# workshop.net
KiCad netlist of a schematic drawn in EAGLE
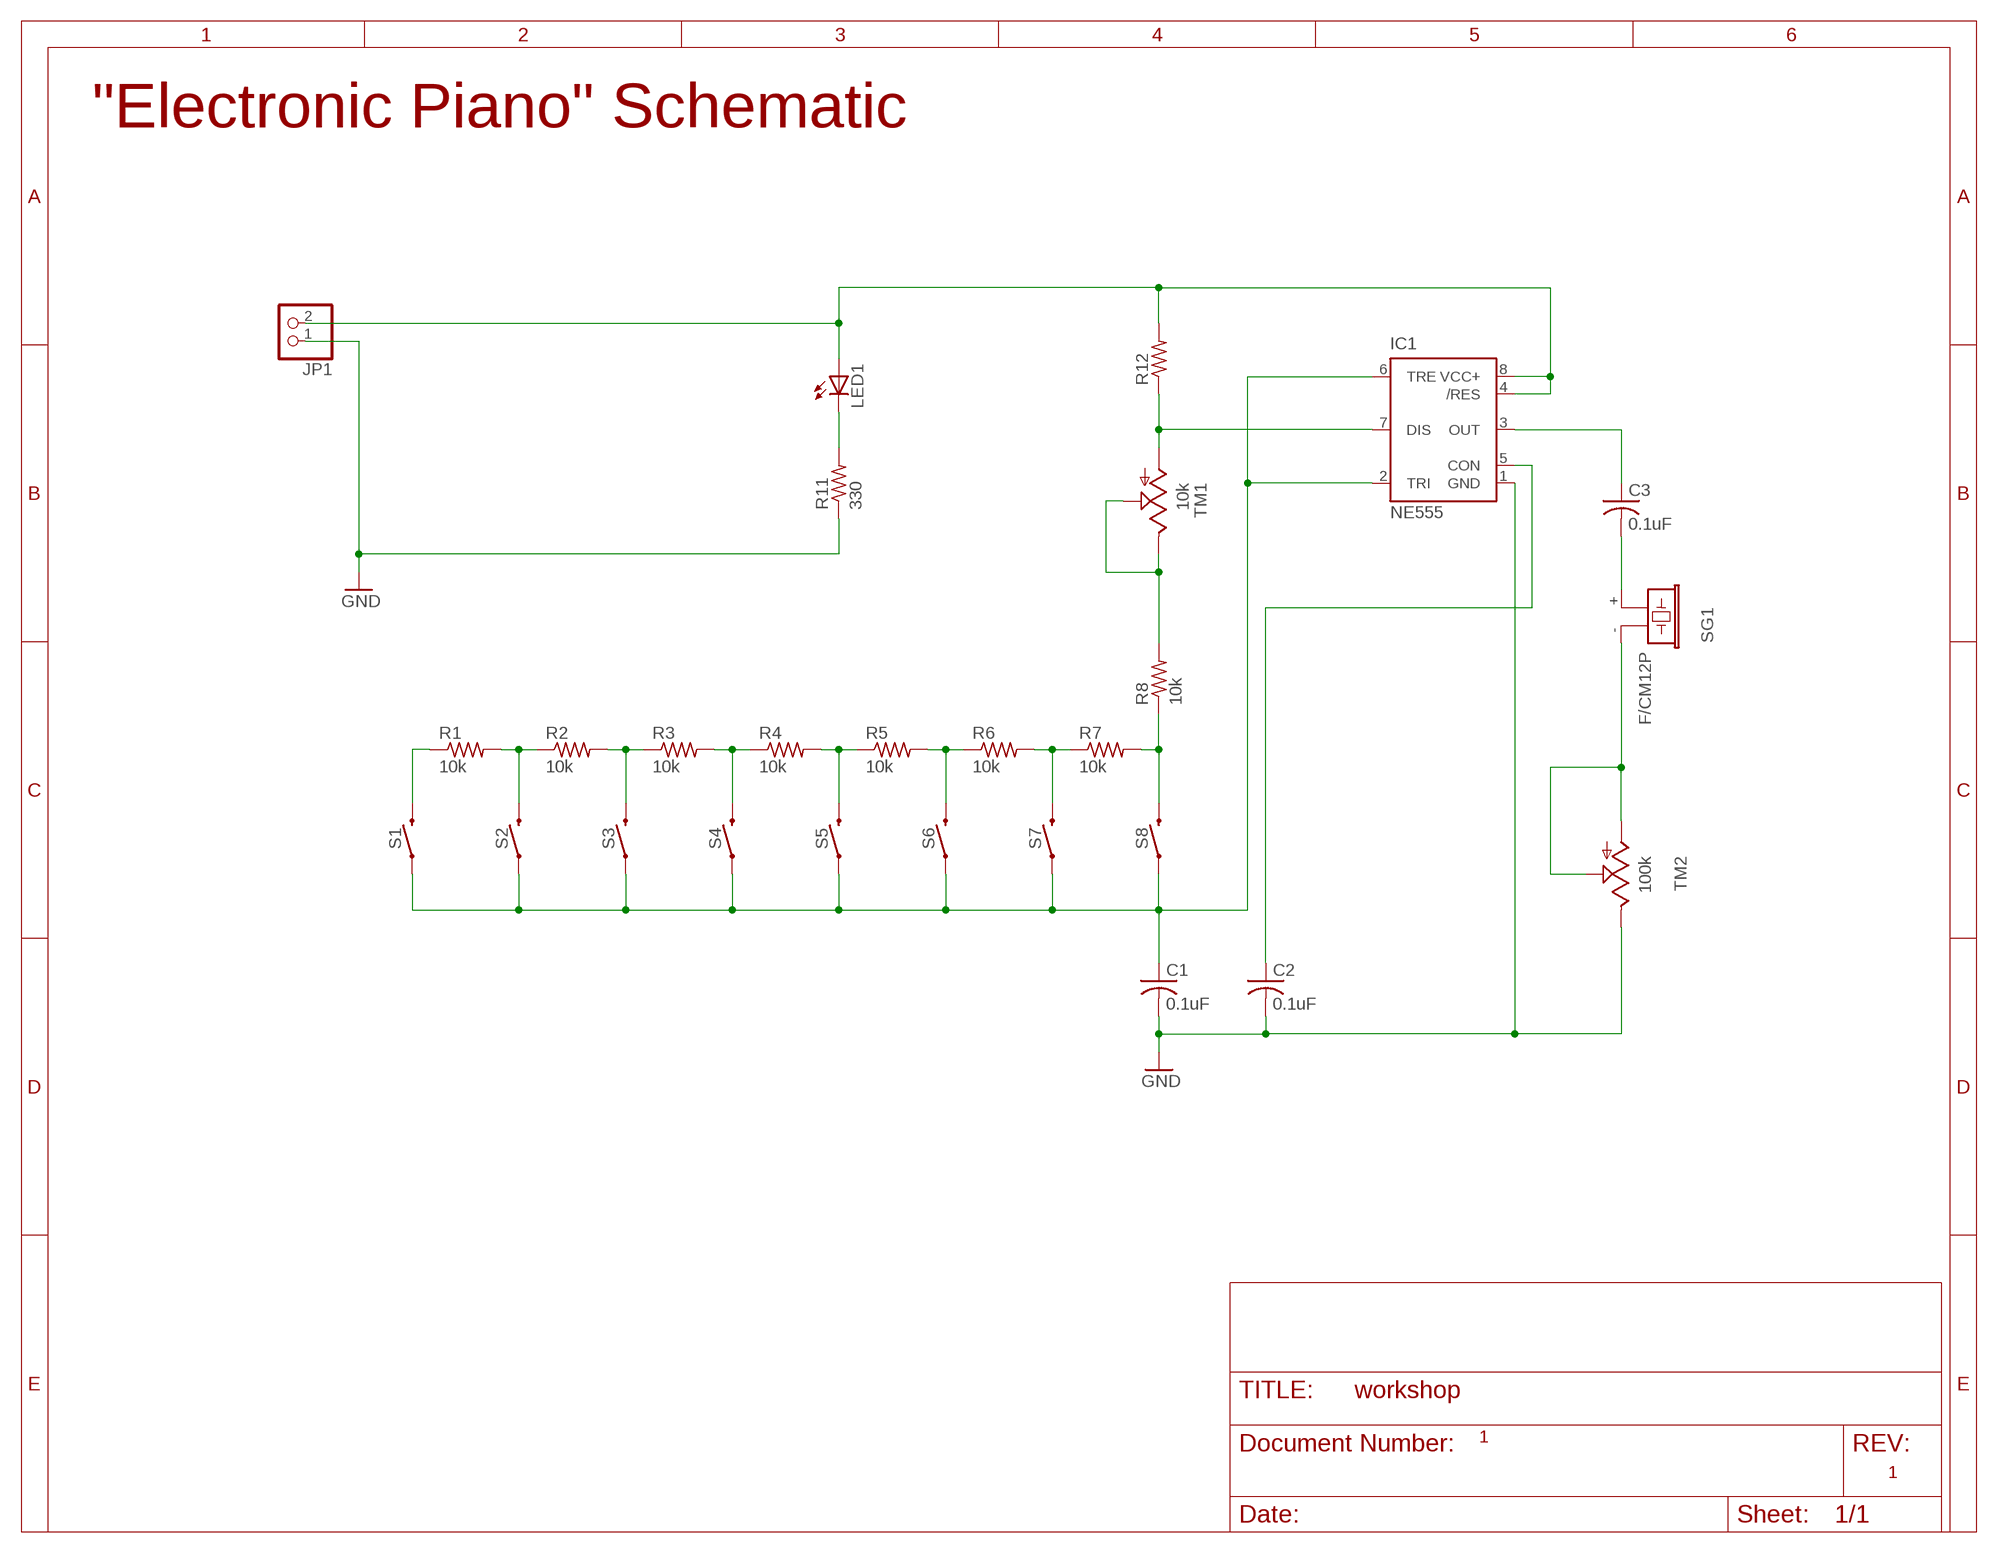
[diagram p0: schematic, sheet 1]

(export (version "E")
  (design (tool "Eeschema 10.0.6"))
  (components
    (comp (ref "C1")
      (value "0.1uF")
      (footprint "eagle-import:C025-040X050")
      (libsource (lib "eagle-import") (part "C-US025-040X050"))
    )
    (comp (ref "C2")
      (value "0.1uF")
      (footprint "eagle-import:C025-040X050")
      (libsource (lib "eagle-import") (part "C-US025-040X050"))
    )
    (comp (ref "C3")
      (value "0.1uF")
      (footprint "eagle-import:C025-040X050")
      (libsource (lib "eagle-import") (part "C-US025-040X050"))
    )
    (comp (ref "IC1")
      (value "NE555")
      (footprint "eagle-import:DIL-08")
      (fields (field (name "MF") "Arrow Electronics") (field (name "MPN") "NE555N"))
      (libsource (lib "eagle-import") (part "NE555"))
    )
    (comp (ref "JP1")
      (value "PINHD-1X2")
      (footprint "eagle-import:1X02")
      (libsource (lib "eagle-import") (part "PINHD-1X2"))
    )
    (comp (ref "LED1")
      (value "LED5MM")
      (footprint "eagle-import:LED5MM")
      (libsource (lib "eagle-import") (part "LED5MM"))
    )
    (comp (ref "R1")
      (value "10k")
      (footprint "eagle-import:0207_7")
      (libsource (lib "eagle-import") (part "R-US_0207/7"))
    )
    (comp (ref "R2")
      (value "10k")
      (footprint "eagle-import:0207_7")
      (libsource (lib "eagle-import") (part "R-US_0207/7"))
    )
    (comp (ref "R3")
      (value "10k")
      (footprint "eagle-import:0207_7")
      (libsource (lib "eagle-import") (part "R-US_0207/7"))
    )
    (comp (ref "R4")
      (value "10k")
      (footprint "eagle-import:0207_7")
      (libsource (lib "eagle-import") (part "R-US_0207/7"))
    )
    (comp (ref "R5")
      (value "10k")
      (footprint "eagle-import:0207_7")
      (libsource (lib "eagle-import") (part "R-US_0207/7"))
    )
    (comp (ref "R6")
      (value "10k")
      (footprint "eagle-import:0207_7")
      (libsource (lib "eagle-import") (part "R-US_0207/7"))
    )
    (comp (ref "R7")
      (value "10k")
      (footprint "eagle-import:0207_7")
      (libsource (lib "eagle-import") (part "R-US_0207/7"))
    )
    (comp (ref "R8")
      (value "10k")
      (footprint "eagle-import:0207_7")
      (libsource (lib "eagle-import") (part "R-US_0207/7"))
    )
    (comp (ref "R11")
      (value "330")
      (footprint "eagle-import:0207_7")
      (libsource (lib "eagle-import") (part "R-US_0207/7"))
    )
    (comp (ref "R12")
      (value "R-US_0207/7")
      (footprint "eagle-import:0207_7")
      (libsource (lib "eagle-import") (part "R-US_0207/7"))
    )
    (comp (ref "S1")
      (value "MOMENTARY-SWITCH-SPST-PTH-6.0MM")
      (footprint "eagle-import:TACTILE_SWITCH_PTH_6.0MM")
      (libsource (lib "eagle-import") (part "MOMENTARY-SWITCH-SPST-PTH-6.0MM"))
    )
    (comp (ref "S2")
      (value "MOMENTARY-SWITCH-SPST-PTH-6.0MM")
      (footprint "eagle-import:TACTILE_SWITCH_PTH_6.0MM")
      (libsource (lib "eagle-import") (part "MOMENTARY-SWITCH-SPST-PTH-6.0MM"))
    )
    (comp (ref "S3")
      (value "MOMENTARY-SWITCH-SPST-PTH-6.0MM")
      (footprint "eagle-import:TACTILE_SWITCH_PTH_6.0MM")
      (libsource (lib "eagle-import") (part "MOMENTARY-SWITCH-SPST-PTH-6.0MM"))
    )
    (comp (ref "S4")
      (value "MOMENTARY-SWITCH-SPST-PTH-6.0MM")
      (footprint "eagle-import:TACTILE_SWITCH_PTH_6.0MM")
      (libsource (lib "eagle-import") (part "MOMENTARY-SWITCH-SPST-PTH-6.0MM"))
    )
    (comp (ref "S5")
      (value "MOMENTARY-SWITCH-SPST-PTH-6.0MM")
      (footprint "eagle-import:TACTILE_SWITCH_PTH_6.0MM")
      (libsource (lib "eagle-import") (part "MOMENTARY-SWITCH-SPST-PTH-6.0MM"))
    )
    (comp (ref "S6")
      (value "MOMENTARY-SWITCH-SPST-PTH-6.0MM")
      (footprint "eagle-import:TACTILE_SWITCH_PTH_6.0MM")
      (libsource (lib "eagle-import") (part "MOMENTARY-SWITCH-SPST-PTH-6.0MM"))
    )
    (comp (ref "S7")
      (value "MOMENTARY-SWITCH-SPST-PTH-6.0MM")
      (footprint "eagle-import:TACTILE_SWITCH_PTH_6.0MM")
      (libsource (lib "eagle-import") (part "MOMENTARY-SWITCH-SPST-PTH-6.0MM"))
    )
    (comp (ref "S8")
      (value "MOMENTARY-SWITCH-SPST-PTH-6.0MM")
      (footprint "eagle-import:TACTILE_SWITCH_PTH_6.0MM")
      (libsource (lib "eagle-import") (part "MOMENTARY-SWITCH-SPST-PTH-6.0MM"))
    )
    (comp (ref "SG1")
      (value "F/CM12P")
      (footprint "eagle-import:F_CM12P")
      (libsource (lib "eagle-import") (part "F/CM12P"))
    )
    (comp (ref "TM1")
      (value "10k")
      (footprint "eagle-import:6MM")
      (libsource (lib "eagle-import") (part "TRIM"))
    )
    (comp (ref "TM2")
      (value "100k")
      (footprint "eagle-import:6MM")
      (libsource (lib "eagle-import") (part "TRIM"))
    )
  )
  (nets
    (net (code "1") (name "GND") (class "Default")
      (node (ref "C1") (pin "2") (pinfunction "2_2") (pintype "passive"))
      (node (ref "C2") (pin "2") (pinfunction "2_2") (pintype "passive"))
      (node (ref "IC1") (pin "1") (pinfunction "GND_1") (pintype "power_in"))
      (node (ref "JP1") (pin "1") (pinfunction "1_1") (pintype "passive"))
      (node (ref "R11") (pin "1") (pinfunction "1_1") (pintype "passive"))
      (node (ref "TM2") (pin "E") (pinfunction "E_E") (pintype "passive"))
    )
    (net (code "2") (name "Net-(IC1-CON)") (class "Default")
      (node (ref "C2") (pin "1") (pinfunction "1_1") (pintype "passive"))
      (node (ref "IC1") (pin "5") (pinfunction "CON_5") (pintype "input"))
    )
    (net (code "3") (name "Net-(IC1-DIS)") (class "Default")
      (node (ref "IC1") (pin "7") (pinfunction "DIS_7") (pintype "input"))
      (node (ref "R12") (pin "1") (pinfunction "1_1") (pintype "passive"))
      (node (ref "TM1") (pin "A") (pinfunction "A_A") (pintype "passive"))
    )
    (net (code "4") (name "Net-(IC1-OUT)") (class "Default")
      (node (ref "C3") (pin "1") (pinfunction "1_1") (pintype "passive"))
      (node (ref "IC1") (pin "3") (pinfunction "OUT_3") (pintype "output"))
    )
    (net (code "5") (name "Net-(IC1-TRE)") (class "Default")
      (node (ref "C1") (pin "1") (pinfunction "1_1") (pintype "passive"))
      (node (ref "IC1") (pin "2") (pinfunction "TRI_2") (pintype "input"))
      (node (ref "IC1") (pin "6") (pinfunction "TRE_6") (pintype "input"))
      (node (ref "S1") (pin "1") (pinfunction "1_1") (pintype "passive"))
      (node (ref "S2") (pin "1") (pinfunction "1_1") (pintype "passive"))
      (node (ref "S3") (pin "1") (pinfunction "1_1") (pintype "passive"))
      (node (ref "S4") (pin "1") (pinfunction "1_1") (pintype "passive"))
      (node (ref "S5") (pin "1") (pinfunction "1_1") (pintype "passive"))
      (node (ref "S6") (pin "1") (pinfunction "1_1") (pintype "passive"))
      (node (ref "S7") (pin "1") (pinfunction "1_1") (pintype "passive"))
      (node (ref "S8") (pin "1") (pinfunction "1_1") (pintype "passive"))
    )
    (net (code "6") (name "Net-(IC1-VCC+)") (class "Default")
      (node (ref "IC1") (pin "4") (pinfunction "/RES_4") (pintype "input"))
      (node (ref "IC1") (pin "8") (pinfunction "VCC+_8") (pintype "power_in"))
      (node (ref "JP1") (pin "2") (pinfunction "2_2") (pintype "passive"))
      (node (ref "LED1") (pin "A") (pinfunction "A_A") (pintype "passive"))
      (node (ref "R12") (pin "2") (pinfunction "2_2") (pintype "passive"))
    )
    (net (code "7") (name "Net-(LED1-C)") (class "Default")
      (node (ref "LED1") (pin "K") (pinfunction "C_K") (pintype "passive"))
      (node (ref "R11") (pin "2") (pinfunction "2_2") (pintype "passive"))
    )
    (net (code "8") (name "Net-(R8-Pad2)") (class "Default")
      (node (ref "R8") (pin "2") (pinfunction "2_2") (pintype "passive"))
      (node (ref "TM1") (pin "E") (pinfunction "E_E") (pintype "passive"))
      (node (ref "TM1") (pin "S") (pinfunction "S_S") (pintype "passive"))
    )
    (net (code "9") (name "Net-(S1-2)") (class "Default")
      (node (ref "R1") (pin "1") (pinfunction "1_1") (pintype "passive"))
      (node (ref "S1") (pin "3") (pinfunction "2_3") (pintype "passive"))
    )
    (net (code "10") (name "Net-(S2-2)") (class "Default")
      (node (ref "R1") (pin "2") (pinfunction "2_2") (pintype "passive"))
      (node (ref "R2") (pin "1") (pinfunction "1_1") (pintype "passive"))
      (node (ref "S2") (pin "3") (pinfunction "2_3") (pintype "passive"))
    )
    (net (code "11") (name "Net-(S3-2)") (class "Default")
      (node (ref "R2") (pin "2") (pinfunction "2_2") (pintype "passive"))
      (node (ref "R3") (pin "1") (pinfunction "1_1") (pintype "passive"))
      (node (ref "S3") (pin "3") (pinfunction "2_3") (pintype "passive"))
    )
    (net (code "12") (name "Net-(S4-2)") (class "Default")
      (node (ref "R3") (pin "2") (pinfunction "2_2") (pintype "passive"))
      (node (ref "R4") (pin "1") (pinfunction "1_1") (pintype "passive"))
      (node (ref "S4") (pin "3") (pinfunction "2_3") (pintype "passive"))
    )
    (net (code "13") (name "Net-(S5-2)") (class "Default")
      (node (ref "R4") (pin "2") (pinfunction "2_2") (pintype "passive"))
      (node (ref "R5") (pin "1") (pinfunction "1_1") (pintype "passive"))
      (node (ref "S5") (pin "3") (pinfunction "2_3") (pintype "passive"))
    )
    (net (code "14") (name "Net-(S6-2)") (class "Default")
      (node (ref "R5") (pin "2") (pinfunction "2_2") (pintype "passive"))
      (node (ref "R6") (pin "1") (pinfunction "1_1") (pintype "passive"))
      (node (ref "S6") (pin "3") (pinfunction "2_3") (pintype "passive"))
    )
    (net (code "15") (name "Net-(S7-2)") (class "Default")
      (node (ref "R6") (pin "2") (pinfunction "2_2") (pintype "passive"))
      (node (ref "R7") (pin "1") (pinfunction "1_1") (pintype "passive"))
      (node (ref "S7") (pin "3") (pinfunction "2_3") (pintype "passive"))
    )
    (net (code "16") (name "Net-(S8-2)") (class "Default")
      (node (ref "R7") (pin "2") (pinfunction "2_2") (pintype "passive"))
      (node (ref "R8") (pin "1") (pinfunction "1_1") (pintype "passive"))
      (node (ref "S8") (pin "3") (pinfunction "2_3") (pintype "passive"))
    )
    (net (code "17") (name "Net-(SG1-1)") (class "Default")
      (node (ref "C3") (pin "2") (pinfunction "2_2") (pintype "passive"))
      (node (ref "SG1") (pin "+") (pinfunction "1_+") (pintype "passive"))
    )
    (net (code "18") (name "Net-(SG1-2)") (class "Default")
      (node (ref "SG1") (pin "-") (pinfunction "2_-") (pintype "passive"))
      (node (ref "TM2") (pin "A") (pinfunction "A_A") (pintype "passive"))
      (node (ref "TM2") (pin "S") (pinfunction "S_S") (pintype "passive"))
    )
  )
)
